# imu.net
KiCad netlist of a schematic drawn in EAGLE
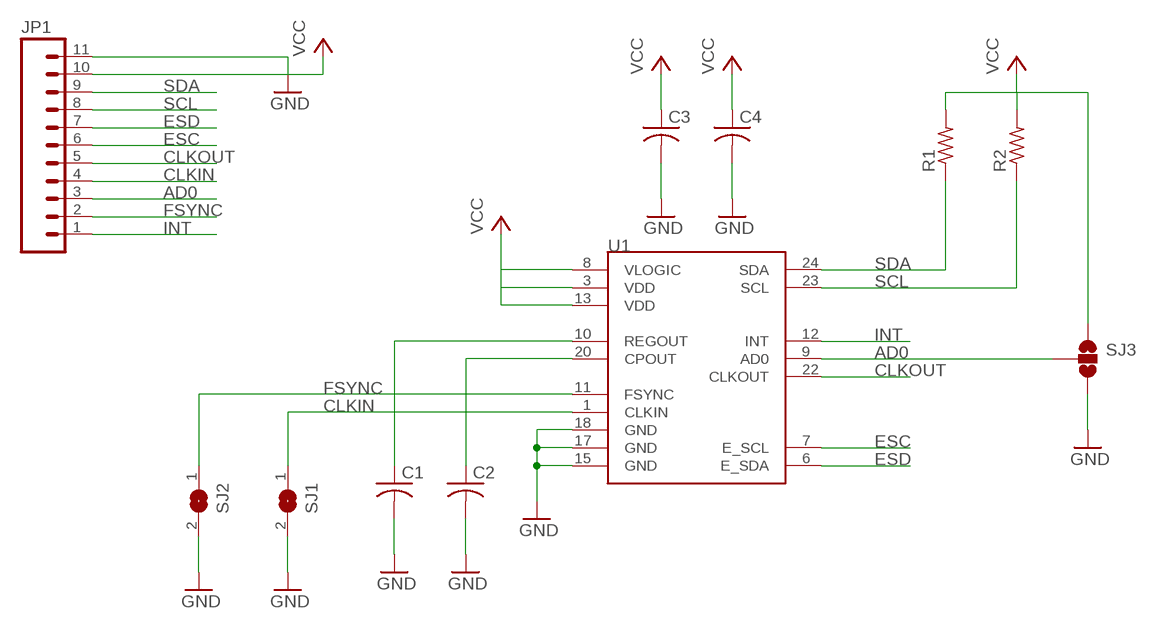
[diagram p0: schematic, sheet 1]

(export (version "E")
  (design (tool "Eeschema 10.0.6"))
  (components
    (comp (ref "C1")
      (value "C-USC0805")
      (footprint "eagle-import:C0805")
      (libsource (lib "eagle-import") (part "C-USC0805"))
    )
    (comp (ref "C2")
      (value "C-USC0805")
      (footprint "eagle-import:C0805")
      (libsource (lib "eagle-import") (part "C-USC0805"))
    )
    (comp (ref "C3")
      (value "C-USC0805")
      (footprint "eagle-import:C0805")
      (libsource (lib "eagle-import") (part "C-USC0805"))
    )
    (comp (ref "C4")
      (value "C-USC0805")
      (footprint "eagle-import:C0805")
      (libsource (lib "eagle-import") (part "C-USC0805"))
    )
    (comp (ref "JP1")
      (value "M11PTH")
      (footprint "eagle-import:1X11")
      (libsource (lib "eagle-import") (part "M11PTH"))
    )
    (comp (ref "R1")
      (value "R-US_R0805")
      (footprint "eagle-import:R0805")
      (libsource (lib "eagle-import") (part "R-US_R0805"))
    )
    (comp (ref "R2")
      (value "R-US_R0805")
      (footprint "eagle-import:R0805")
      (libsource (lib "eagle-import") (part "R-US_R0805"))
    )
    (comp (ref "SJ1") (value "SJ") (footprint "eagle-import:SJ") (libsource (lib "eagle-import") (part "SJ")))
    (comp (ref "SJ2") (value "SJ") (footprint "eagle-import:SJ") (libsource (lib "eagle-import") (part "SJ")))
    (comp (ref "SJ3")
      (value "SOLDERJUMPER_2WAY-OLDW")
      (footprint "eagle-import:SJ_2W")
      (libsource (lib "eagle-import") (part "SOLDERJUMPER_2WAY-OLDW"))
    )
    (comp (ref "U1")
      (value "MPU-9150QFN-24-NP")
      (footprint "eagle-import:QFN-24-NP")
      (libsource (lib "eagle-import") (part "MPU-9150QFN-24-NP"))
    )
  )
  (nets
    (net (code "1") (name "/AD0") (class "Default")
      (node (ref "JP1") (pin "3") (pinfunction "3_3") (pintype "passive"))
      (node (ref "SJ3") (pin "2") (pinfunction "2_2") (pintype "passive"))
      (node (ref "U1") (pin "9") (pinfunction "AD0_9") (pintype "bidirectional"))
    )
    (net (code "2") (name "/CLKIN") (class "Default")
      (node (ref "JP1") (pin "4") (pinfunction "4_4") (pintype "passive"))
      (node (ref "SJ1") (pin "1") (pinfunction "1_1") (pintype "passive"))
      (node (ref "U1") (pin "1") (pinfunction "CLKIN_1") (pintype "bidirectional"))
    )
    (net (code "3") (name "/CLKOUT") (class "Default")
      (node (ref "JP1") (pin "5") (pinfunction "5_5") (pintype "passive"))
      (node (ref "U1") (pin "22") (pinfunction "CLKOUT_22") (pintype "bidirectional"))
    )
    (net (code "4") (name "/ESC") (class "Default")
      (node (ref "JP1") (pin "6") (pinfunction "6_6") (pintype "passive"))
      (node (ref "U1") (pin "7") (pinfunction "E_SCL_7") (pintype "bidirectional"))
    )
    (net (code "5") (name "/ESD") (class "Default")
      (node (ref "JP1") (pin "7") (pinfunction "7_7") (pintype "passive"))
      (node (ref "U1") (pin "6") (pinfunction "E_SDA_6") (pintype "bidirectional"))
    )
    (net (code "6") (name "/FSYNC") (class "Default")
      (node (ref "JP1") (pin "2") (pinfunction "2_2") (pintype "passive"))
      (node (ref "SJ2") (pin "1") (pinfunction "1_1") (pintype "passive"))
      (node (ref "U1") (pin "11") (pinfunction "FSYNC_11") (pintype "bidirectional"))
    )
    (net (code "7") (name "/INT") (class "Default")
      (node (ref "JP1") (pin "1") (pinfunction "1_1") (pintype "passive"))
      (node (ref "U1") (pin "12") (pinfunction "INT_12") (pintype "bidirectional"))
    )
    (net (code "8") (name "/SCL") (class "Default")
      (node (ref "JP1") (pin "8") (pinfunction "8_8") (pintype "passive"))
      (node (ref "R2") (pin "1") (pinfunction "1_1") (pintype "passive"))
      (node (ref "U1") (pin "23") (pinfunction "SCL_23") (pintype "bidirectional"))
    )
    (net (code "9") (name "/SDA") (class "Default")
      (node (ref "JP1") (pin "9") (pinfunction "9_9") (pintype "passive"))
      (node (ref "R1") (pin "1") (pinfunction "1_1") (pintype "passive"))
      (node (ref "U1") (pin "24") (pinfunction "SDA_24") (pintype "bidirectional"))
    )
    (net (code "10") (name "GND") (class "Default")
      (node (ref "C1") (pin "2") (pinfunction "2_2") (pintype "passive"))
      (node (ref "C2") (pin "2") (pinfunction "2_2") (pintype "passive"))
      (node (ref "C3") (pin "2") (pinfunction "2_2") (pintype "passive"))
      (node (ref "C4") (pin "2") (pinfunction "2_2") (pintype "passive"))
      (node (ref "JP1") (pin "11") (pinfunction "11_11") (pintype "passive"))
      (node (ref "SJ1") (pin "2") (pinfunction "2_2") (pintype "passive"))
      (node (ref "SJ2") (pin "2") (pinfunction "2_2") (pintype "passive"))
      (node (ref "SJ3") (pin "3") (pinfunction "3_3") (pintype "passive"))
      (node (ref "U1") (pin "15") (pinfunction "GND_15") (pintype "bidirectional"))
      (node (ref "U1") (pin "17") (pinfunction "GND_17") (pintype "bidirectional"))
      (node (ref "U1") (pin "18") (pinfunction "GND_18") (pintype "bidirectional"))
    )
    (net (code "11") (name "Net-(U1-CPOUT)") (class "Default")
      (node (ref "C2") (pin "1") (pinfunction "1_1") (pintype "passive"))
      (node (ref "U1") (pin "20") (pinfunction "CPOUT_20") (pintype "bidirectional"))
    )
    (net (code "12") (name "Net-(U1-REGOUT)") (class "Default")
      (node (ref "C1") (pin "1") (pinfunction "1_1") (pintype "passive"))
      (node (ref "U1") (pin "10") (pinfunction "REGOUT_10") (pintype "bidirectional"))
    )
    (net (code "13") (name "VCC") (class "Default")
      (node (ref "C3") (pin "1") (pinfunction "1_1") (pintype "passive"))
      (node (ref "C4") (pin "1") (pinfunction "1_1") (pintype "passive"))
      (node (ref "JP1") (pin "10") (pinfunction "10_10") (pintype "passive"))
      (node (ref "R1") (pin "2") (pinfunction "2_2") (pintype "passive"))
      (node (ref "R2") (pin "2") (pinfunction "2_2") (pintype "passive"))
      (node (ref "SJ3") (pin "1") (pinfunction "1_1") (pintype "passive"))
      (node (ref "U1") (pin "13") (pinfunction "VDD_13") (pintype "bidirectional"))
      (node (ref "U1") (pin "3") (pinfunction "VDD_3") (pintype "bidirectional"))
      (node (ref "U1") (pin "8") (pinfunction "VLOGIC_8") (pintype "bidirectional"))
    )
  )
)
